# OpAmp_NonInvertente_V2.net
KiCad netlist of a schematic drawn in EAGLE
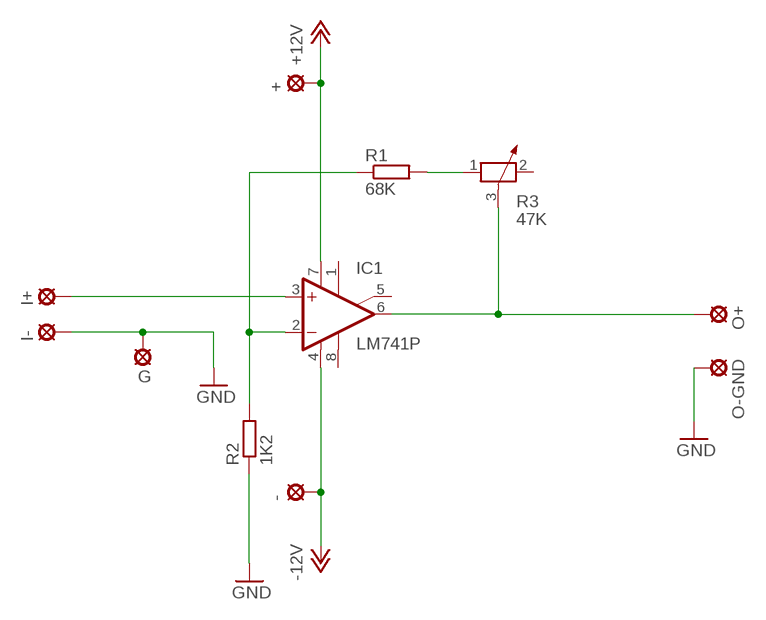
[diagram p0: schematic, sheet 1]

(export (version "E")
  (design (tool "Eeschema 10.0.6"))
  (components
    (comp (ref "+")
      (value "LSP10")
      (footprint "eagle-import:LSP10")
      (libsource (lib "eagle-import") (part "LSP10"))
    )
    (comp (ref "-")
      (value "LSP10")
      (footprint "eagle-import:LSP10")
      (libsource (lib "eagle-import") (part "LSP10"))
    )
    (comp (ref "G")
      (value "LSP10")
      (footprint "eagle-import:LSP10")
      (libsource (lib "eagle-import") (part "LSP10"))
    )
    (comp (ref "I+")
      (value "LSP10")
      (footprint "eagle-import:LSP10")
      (libsource (lib "eagle-import") (part "LSP10"))
    )
    (comp (ref "I-")
      (value "LSP10")
      (footprint "eagle-import:LSP10")
      (libsource (lib "eagle-import") (part "LSP10"))
    )
    (comp (ref "IC1")
      (value "LM741P")
      (footprint "eagle-import:DIL08")
      (libsource (lib "eagle-import") (part "741PLM"))
    )
    (comp (ref "O+")
      (value "LSP10")
      (footprint "eagle-import:LSP10")
      (libsource (lib "eagle-import") (part "LSP10"))
    )
    (comp (ref "O-GND")
      (value "LSP10")
      (footprint "eagle-import:LSP10")
      (libsource (lib "eagle-import") (part "LSP10"))
    )
    (comp (ref "R1")
      (value "68K")
      (footprint "eagle-import:0207_12")
      (libsource (lib "eagle-import") (part "R-EU_0207/12"))
    )
    (comp (ref "R2")
      (value "1K2")
      (footprint "eagle-import:0207_12")
      (libsource (lib "eagle-import") (part "R-EU_0207/12"))
    )
    (comp (ref "R3")
      (value "47K")
      (footprint "eagle-import:PT-10")
      (libsource (lib "eagle-import") (part "POTENTIOMETER_PT-10"))
    )
  )
  (nets
    (net (code "1") (name "+12V") (class "Default")
      (node (ref "+") (pin "MP") (pinfunction "MP_MP") (pintype "passive"))
      (node (ref "IC1") (pin "7") (pinfunction "V+_7") (pintype "power_in"))
    )
    (net (code "2") (name "-12V") (class "Default")
      (node (ref "-") (pin "MP") (pinfunction "MP_MP") (pintype "passive"))
      (node (ref "IC1") (pin "4") (pinfunction "V-_4") (pintype "power_in"))
    )
    (net (code "3") (name "GND") (class "Default")
      (node (ref "G") (pin "MP") (pinfunction "MP_MP") (pintype "passive"))
      (node (ref "I-") (pin "MP") (pinfunction "MP_MP") (pintype "passive"))
      (node (ref "O-GND") (pin "MP") (pinfunction "MP_MP") (pintype "passive"))
      (node (ref "R2") (pin "1") (pinfunction "1_1") (pintype "passive"))
    )
    (net (code "4") (name "Net-(IC1-+IN)") (class "Default")
      (node (ref "I+") (pin "MP") (pinfunction "MP_MP") (pintype "passive"))
      (node (ref "IC1") (pin "3") (pinfunction "+IN_3") (pintype "input"))
    )
    (net (code "5") (name "Net-(IC1--IN)") (class "Default")
      (node (ref "IC1") (pin "2") (pinfunction "-IN_2") (pintype "input"))
      (node (ref "R1") (pin "1") (pinfunction "1_1") (pintype "passive"))
      (node (ref "R2") (pin "2") (pinfunction "2_2") (pintype "passive"))
    )
    (net (code "6") (name "Net-(IC1-OUT)") (class "Default")
      (node (ref "IC1") (pin "6") (pinfunction "OUT_6") (pintype "output"))
      (node (ref "O+") (pin "MP") (pinfunction "MP_MP") (pintype "passive"))
      (node (ref "R3") (pin "3") (pinfunction "3_3") (pintype "passive"))
    )
    (net (code "7") (name "Net-(R1-Pad2)") (class "Default")
      (node (ref "R1") (pin "2") (pinfunction "2_2") (pintype "passive"))
      (node (ref "R3") (pin "1") (pinfunction "1_1") (pintype "passive"))
    )
    (net (code "8") (name "unconnected-(IC1-ON1-Pad1)") (class "Default")
      (node (ref "IC1") (pin "1") (pinfunction "ON1_1") (pintype "passive"))
    )
    (net (code "9") (name "unconnected-(IC1-ON2-Pad5)") (class "Default")
      (node (ref "IC1") (pin "5") (pinfunction "ON2_5") (pintype "passive"))
    )
    (net (code "10") (name "unconnected-(IC1-OPT-Pad8)") (class "Default")
      (node (ref "IC1") (pin "8") (pinfunction "OPT_8") (pintype "passive"))
    )
    (net (code "11") (name "unconnected-(R3-Pad2)") (class "Default")
      (node (ref "R3") (pin "2") (pinfunction "2_2") (pintype "passive"))
    )
  )
)
